# HSNetmeter-simple-v1_1.net
KiCad netlist of a schematic drawn in EAGLE
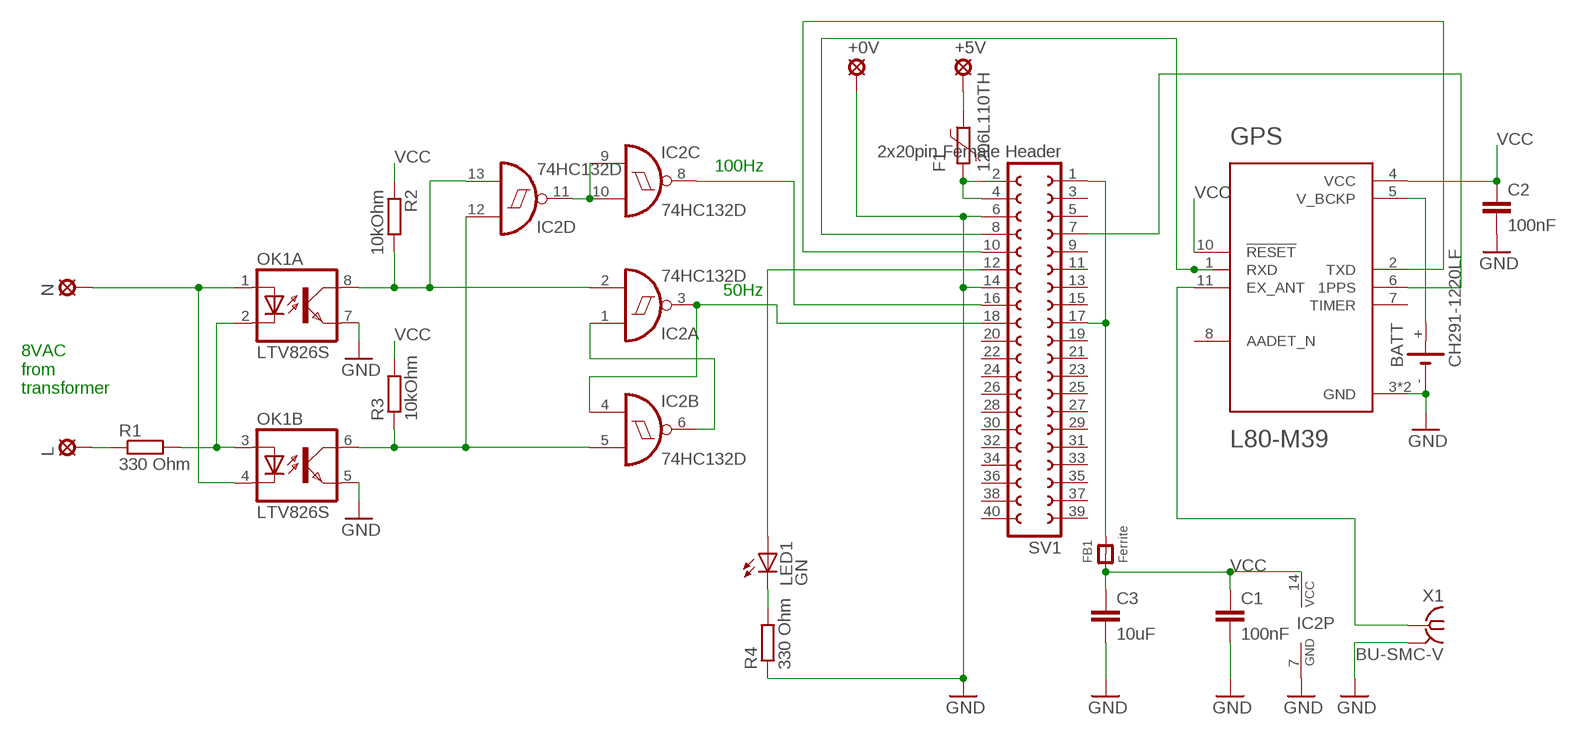
[diagram p0: schematic, sheet 1]

(export (version "E")
  (design (tool "Eeschema 10.0.6"))
  (components
    (comp (ref "+0V")
      (value "LSP11")
      (footprint "eagle-import:LSP11")
      (libsource (lib "eagle-import") (part "LSP11"))
    )
    (comp (ref "+5V")
      (value "LSP11")
      (footprint "eagle-import:LSP11")
      (libsource (lib "eagle-import") (part "LSP11"))
    )
    (comp (ref "BATT")
      (value "CH291-1220LF")
      (footprint "eagle-import:CH291-1220LF")
      (libsource (lib "eagle-import") (part "CH291-1220LF"))
    )
    (comp (ref "C1")
      (value "100nF")
      (footprint "eagle-import:C0805")
      (libsource (lib "eagle-import") (part "C-EUC0805"))
    )
    (comp (ref "C2")
      (value "100nF")
      (footprint "eagle-import:C0805")
      (libsource (lib "eagle-import") (part "C-EUC0805"))
    )
    (comp (ref "C3")
      (value "10uF")
      (footprint "eagle-import:C1206")
      (libsource (lib "eagle-import") (part "C-EUC1206"))
    )
    (comp (ref "F1")
      (value "1206L110TH")
      (footprint "eagle-import:1206L")
      (fields (field (name "MF") "Littelfuse"))
      (libsource (lib "eagle-import") (part "?1206L110TH"))
    )
    (comp (ref "FB1")
      (value "Ferrite")
      (footprint "eagle-import:0805")
      (libsource (lib "eagle-import") (part "FERRITE0805"))
    )
    (comp (ref "GPS")
      (value "L80-M39")
      (footprint "eagle-import:QUECTEL_L80-M39")
      (fields (field (name "MF") "Quectel"))
      (libsource (lib "eagle-import") (part "L80-M39"))
    )
    (comp (ref "IC2")
      (value "74HC132D")
      (footprint "eagle-import:SO14")
      (libsource (lib "eagle-import") (part "74132DHC"))
    )
    (comp (ref "L")
      (value "LSP11")
      (footprint "eagle-import:LSP11")
      (libsource (lib "eagle-import") (part "LSP11"))
    )
    (comp (ref "LED1")
      (value "GN")
      (footprint "eagle-import:LED3MM")
      (libsource (lib "eagle-import") (part "LED3MM"))
    )
    (comp (ref "N")
      (value "LSP11")
      (footprint "eagle-import:LSP11")
      (libsource (lib "eagle-import") (part "LSP11"))
    )
    (comp (ref "OK1")
      (value "LTV826S")
      (footprint "eagle-import:DIL8-SMD")
      (libsource (lib "eagle-import") (part "LTV826S"))
    )
    (comp (ref "R1")
      (value "330 Ohm")
      (footprint "eagle-import:M0805")
      (libsource (lib "eagle-import") (part "R-EU_M0805"))
    )
    (comp (ref "R2")
      (value "10kOhm")
      (footprint "eagle-import:M0805")
      (libsource (lib "eagle-import") (part "R-EU_M0805"))
    )
    (comp (ref "R3")
      (value "10kOhm")
      (footprint "eagle-import:M0805")
      (libsource (lib "eagle-import") (part "R-EU_M0805"))
    )
    (comp (ref "R4")
      (value "330 Ohm")
      (footprint "eagle-import:M0805")
      (libsource (lib "eagle-import") (part "R-EU_M0805"))
    )
    (comp (ref "SV1")
      (value "2x20pin Female Header")
      (footprint "eagle-import:FE20-2")
      (libsource (lib "eagle-import") (part "FE20-2"))
    )
    (comp (ref "X1")
      (value "BU-SMC-V")
      (footprint "eagle-import:BU-SMC-V")
      (libsource (lib "eagle-import") (part "BU-SMC-V"))
    )
  )
  (nets
    (net (code "1") (name "/VCC") (class "Default")
      (node (ref "C1") (pin "1") (pinfunction "1_1") (pintype "passive"))
      (node (ref "C2") (pin "1") (pinfunction "1_1") (pintype "passive"))
      (node (ref "C3") (pin "1") (pinfunction "1_1") (pintype "passive"))
      (node (ref "FB1") (pin "1") (pinfunction "P$1_1") (pintype "passive"))
      (node (ref "GPS") (pin "10") (pinfunction "~{RESET}_10") (pintype "input"))
      (node (ref "GPS") (pin "4") (pinfunction "VCC_4") (pintype "power_in"))
      (node (ref "IC2") (pin "14") (pinfunction "VCC_14") (pintype "power_in"))
      (node (ref "R2") (pin "1") (pinfunction "1_1") (pintype "passive"))
      (node (ref "R3") (pin "2") (pinfunction "2_2") (pintype "passive"))
    )
    (net (code "2") (name "GND") (class "Default")
      (node (ref "+0V") (pin "MP") (pinfunction "MP_MP") (pintype "passive"))
      (node (ref "BATT") (pin "-") (pinfunction "-_-") (pintype "passive"))
      (node (ref "C1") (pin "2") (pinfunction "2_2") (pintype "passive"))
      (node (ref "C2") (pin "2") (pinfunction "2_2") (pintype "passive"))
      (node (ref "C3") (pin "2") (pinfunction "2_2") (pintype "passive"))
      (node (ref "GPS") (pin "12") (pinfunction "GND_12") (pintype "passive"))
      (node (ref "GPS") (pin "3") (pinfunction "GND_3") (pintype "passive"))
      (node (ref "IC2") (pin "7") (pinfunction "GND_7") (pintype "power_in"))
      (node (ref "OK1") (pin "5") (pinfunction "EMIT_5") (pintype "passive"))
      (node (ref "OK1") (pin "7") (pinfunction "EMIT_7") (pintype "passive"))
      (node (ref "R4") (pin "1") (pinfunction "1_1") (pintype "passive"))
      (node (ref "SV1") (pin "14") (pinfunction "14_14") (pintype "passive"))
      (node (ref "SV1") (pin "6") (pinfunction "6_6") (pintype "passive"))
      (node (ref "X1") (pin "2") (pinfunction "2_2") (pintype "passive"))
      (node (ref "X1") (pin "3") (pinfunction "2_3") (pintype "passive"))
      (node (ref "X1") (pin "4") (pinfunction "2_4") (pintype "passive"))
      (node (ref "X1") (pin "5") (pinfunction "2_5") (pintype "passive"))
    )
    (net (code "3") (name "Net-(+5V-PadMP)") (class "Default")
      (node (ref "+5V") (pin "MP") (pinfunction "MP_MP") (pintype "passive"))
      (node (ref "F1") (pin "1") (pinfunction "1_1") (pintype "passive"))
    )
    (net (code "4") (name "Net-(F1-Pad2)") (class "Default")
      (node (ref "F1") (pin "2") (pinfunction "2_2") (pintype "passive"))
      (node (ref "SV1") (pin "2") (pinfunction "2_2") (pintype "passive"))
      (node (ref "SV1") (pin "4") (pinfunction "4_4") (pintype "passive"))
    )
    (net (code "5") (name "Net-(FB1-P$2)") (class "Default")
      (node (ref "FB1") (pin "2") (pinfunction "P$2_2") (pintype "passive"))
      (node (ref "SV1") (pin "1") (pinfunction "1_1") (pintype "passive"))
      (node (ref "SV1") (pin "17") (pinfunction "17_17") (pintype "passive"))
    )
    (net (code "6") (name "Net-(GPS-1PPS)") (class "Default")
      (node (ref "GPS") (pin "6") (pinfunction "1PPS_6") (pintype "output"))
      (node (ref "SV1") (pin "7") (pinfunction "7_7") (pintype "passive"))
    )
    (net (code "7") (name "Net-(GPS-EX_ANT)") (class "Default")
      (node (ref "GPS") (pin "11") (pinfunction "EX_ANT_11") (pintype "input"))
      (node (ref "X1") (pin "1") (pinfunction "1_1") (pintype "passive"))
    )
    (net (code "8") (name "Net-(GPS-RXD)") (class "Default")
      (node (ref "GPS") (pin "1") (pinfunction "RXD_1") (pintype "input"))
      (node (ref "SV1") (pin "8") (pinfunction "8_8") (pintype "passive"))
    )
    (net (code "9") (name "Net-(GPS-TXD)") (class "Default")
      (node (ref "GPS") (pin "2") (pinfunction "TXD_2") (pintype "output"))
      (node (ref "SV1") (pin "10") (pinfunction "10_10") (pintype "passive"))
    )
    (net (code "10") (name "Net-(GPS-V_BCKP)") (class "Default")
      (node (ref "BATT") (pin "+") (pinfunction "+_+") (pintype "passive"))
      (node (ref "GPS") (pin "5") (pinfunction "V_BCKP_5") (pintype "power_in"))
    )
    (net (code "11") (name "Net-(IC2A-I0)") (class "Default")
      (node (ref "IC2") (pin "1") (pinfunction "I0_1") (pintype "input"))
      (node (ref "IC2") (pin "6") (pinfunction "O_6") (pintype "output"))
    )
    (net (code "12") (name "Net-(IC2A-I1)") (class "Default")
      (node (ref "IC2") (pin "13") (pinfunction "I1_13") (pintype "input"))
      (node (ref "IC2") (pin "2") (pinfunction "I1_2") (pintype "input"))
      (node (ref "OK1") (pin "8") (pinfunction "COL_8") (pintype "passive"))
      (node (ref "R2") (pin "2") (pinfunction "2_2") (pintype "passive"))
    )
    (net (code "13") (name "Net-(IC2A-O)") (class "Default")
      (node (ref "IC2") (pin "3") (pinfunction "O_3") (pintype "output"))
      (node (ref "IC2") (pin "4") (pinfunction "I0_4") (pintype "input"))
      (node (ref "SV1") (pin "18") (pinfunction "18_18") (pintype "passive"))
    )
    (net (code "14") (name "Net-(IC2B-I1)") (class "Default")
      (node (ref "IC2") (pin "12") (pinfunction "I0_12") (pintype "input"))
      (node (ref "IC2") (pin "5") (pinfunction "I1_5") (pintype "input"))
      (node (ref "OK1") (pin "6") (pinfunction "COL_6") (pintype "passive"))
      (node (ref "R3") (pin "1") (pinfunction "1_1") (pintype "passive"))
    )
    (net (code "15") (name "Net-(IC2C-I0)") (class "Default")
      (node (ref "IC2") (pin "10") (pinfunction "I1_10") (pintype "input"))
      (node (ref "IC2") (pin "11") (pinfunction "O_11") (pintype "output"))
      (node (ref "IC2") (pin "9") (pinfunction "I0_9") (pintype "input"))
    )
    (net (code "16") (name "Net-(IC2C-O)") (class "Default")
      (node (ref "IC2") (pin "8") (pinfunction "O_8") (pintype "output"))
      (node (ref "SV1") (pin "16") (pinfunction "16_16") (pintype "passive"))
    )
    (net (code "17") (name "Net-(L-PadMP)") (class "Default")
      (node (ref "L") (pin "MP") (pinfunction "MP_MP") (pintype "passive"))
      (node (ref "R1") (pin "1") (pinfunction "1_1") (pintype "passive"))
    )
    (net (code "18") (name "Net-(LED1-C)") (class "Default")
      (node (ref "LED1") (pin "K") (pinfunction "C_K") (pintype "passive"))
      (node (ref "R4") (pin "2") (pinfunction "2_2") (pintype "passive"))
    )
    (net (code "19") (name "Net-(LED1-PadA)") (class "Default")
      (node (ref "LED1") (pin "A") (pinfunction "A_A") (pintype "passive"))
      (node (ref "SV1") (pin "12") (pinfunction "12_12") (pintype "passive"))
    )
    (net (code "20") (name "Net-(OK1A-A)") (class "Default")
      (node (ref "N") (pin "MP") (pinfunction "MP_MP") (pintype "passive"))
      (node (ref "OK1") (pin "1") (pinfunction "A_1") (pintype "passive"))
      (node (ref "OK1") (pin "4") (pinfunction "C_4") (pintype "passive"))
    )
    (net (code "21") (name "Net-(OK1A-C)") (class "Default")
      (node (ref "OK1") (pin "2") (pinfunction "C_2") (pintype "passive"))
      (node (ref "OK1") (pin "3") (pinfunction "A_3") (pintype "passive"))
      (node (ref "R1") (pin "2") (pinfunction "2_2") (pintype "passive"))
    )
    (net (code "22") (name "unconnected-(GPS-AADET_N-Pad8)") (class "Default")
      (node (ref "GPS") (pin "8") (pinfunction "AADET_N_8") (pintype "bidirectional"))
    )
    (net (code "23") (name "unconnected-(GPS-TIMER-Pad7)") (class "Default")
      (node (ref "GPS") (pin "7") (pinfunction "TIMER_7") (pintype "output"))
    )
    (net (code "24") (name "unconnected-(SV1-Pad3)") (class "Default")
      (node (ref "SV1") (pin "3") (pinfunction "3_3") (pintype "passive"))
    )
    (net (code "25") (name "unconnected-(SV1-Pad5)") (class "Default")
      (node (ref "SV1") (pin "5") (pinfunction "5_5") (pintype "passive"))
    )
    (net (code "26") (name "unconnected-(SV1-Pad9)") (class "Default")
      (node (ref "SV1") (pin "9") (pinfunction "9_9") (pintype "passive"))
    )
    (net (code "27") (name "unconnected-(SV1-Pad11)") (class "Default")
      (node (ref "SV1") (pin "11") (pinfunction "11_11") (pintype "passive"))
    )
    (net (code "28") (name "unconnected-(SV1-Pad13)") (class "Default")
      (node (ref "SV1") (pin "13") (pinfunction "13_13") (pintype "passive"))
    )
    (net (code "29") (name "unconnected-(SV1-Pad15)") (class "Default")
      (node (ref "SV1") (pin "15") (pinfunction "15_15") (pintype "passive"))
    )
    (net (code "30") (name "unconnected-(SV1-Pad19)") (class "Default")
      (node (ref "SV1") (pin "19") (pinfunction "19_19") (pintype "passive"))
    )
    (net (code "31") (name "unconnected-(SV1-Pad20)") (class "Default")
      (node (ref "SV1") (pin "20") (pinfunction "20_20") (pintype "passive"))
    )
    (net (code "32") (name "unconnected-(SV1-Pad21)") (class "Default")
      (node (ref "SV1") (pin "21") (pinfunction "21_21") (pintype "passive"))
    )
    (net (code "33") (name "unconnected-(SV1-Pad22)") (class "Default")
      (node (ref "SV1") (pin "22") (pinfunction "22_22") (pintype "passive"))
    )
    (net (code "34") (name "unconnected-(SV1-Pad23)") (class "Default")
      (node (ref "SV1") (pin "23") (pinfunction "23_23") (pintype "passive"))
    )
    (net (code "35") (name "unconnected-(SV1-Pad24)") (class "Default")
      (node (ref "SV1") (pin "24") (pinfunction "24_24") (pintype "passive"))
    )
    (net (code "36") (name "unconnected-(SV1-Pad25)") (class "Default")
      (node (ref "SV1") (pin "25") (pinfunction "25_25") (pintype "passive"))
    )
    (net (code "37") (name "unconnected-(SV1-Pad26)") (class "Default")
      (node (ref "SV1") (pin "26") (pinfunction "26_26") (pintype "passive"))
    )
    (net (code "38") (name "unconnected-(SV1-Pad27)") (class "Default")
      (node (ref "SV1") (pin "27") (pinfunction "27_27") (pintype "passive"))
    )
    (net (code "39") (name "unconnected-(SV1-Pad28)") (class "Default")
      (node (ref "SV1") (pin "28") (pinfunction "28_28") (pintype "passive"))
    )
    (net (code "40") (name "unconnected-(SV1-Pad29)") (class "Default")
      (node (ref "SV1") (pin "29") (pinfunction "29_29") (pintype "passive"))
    )
    (net (code "41") (name "unconnected-(SV1-Pad30)") (class "Default")
      (node (ref "SV1") (pin "30") (pinfunction "30_30") (pintype "passive"))
    )
    (net (code "42") (name "unconnected-(SV1-Pad31)") (class "Default")
      (node (ref "SV1") (pin "31") (pinfunction "31_31") (pintype "passive"))
    )
    (net (code "43") (name "unconnected-(SV1-Pad32)") (class "Default")
      (node (ref "SV1") (pin "32") (pinfunction "32_32") (pintype "passive"))
    )
    (net (code "44") (name "unconnected-(SV1-Pad33)") (class "Default")
      (node (ref "SV1") (pin "33") (pinfunction "33_33") (pintype "passive"))
    )
    (net (code "45") (name "unconnected-(SV1-Pad34)") (class "Default")
      (node (ref "SV1") (pin "34") (pinfunction "34_34") (pintype "passive"))
    )
    (net (code "46") (name "unconnected-(SV1-Pad35)") (class "Default")
      (node (ref "SV1") (pin "35") (pinfunction "35_35") (pintype "passive"))
    )
    (net (code "47") (name "unconnected-(SV1-Pad36)") (class "Default")
      (node (ref "SV1") (pin "36") (pinfunction "36_36") (pintype "passive"))
    )
    (net (code "48") (name "unconnected-(SV1-Pad37)") (class "Default")
      (node (ref "SV1") (pin "37") (pinfunction "37_37") (pintype "passive"))
    )
    (net (code "49") (name "unconnected-(SV1-Pad38)") (class "Default")
      (node (ref "SV1") (pin "38") (pinfunction "38_38") (pintype "passive"))
    )
    (net (code "50") (name "unconnected-(SV1-Pad39)") (class "Default")
      (node (ref "SV1") (pin "39") (pinfunction "39_39") (pintype "passive"))
    )
    (net (code "51") (name "unconnected-(SV1-Pad40)") (class "Default")
      (node (ref "SV1") (pin "40") (pinfunction "40_40") (pintype "passive"))
    )
  )
)
